# 07_LMS7002M_Power.net
KiCad netlist of a schematic drawn in Altium Designer
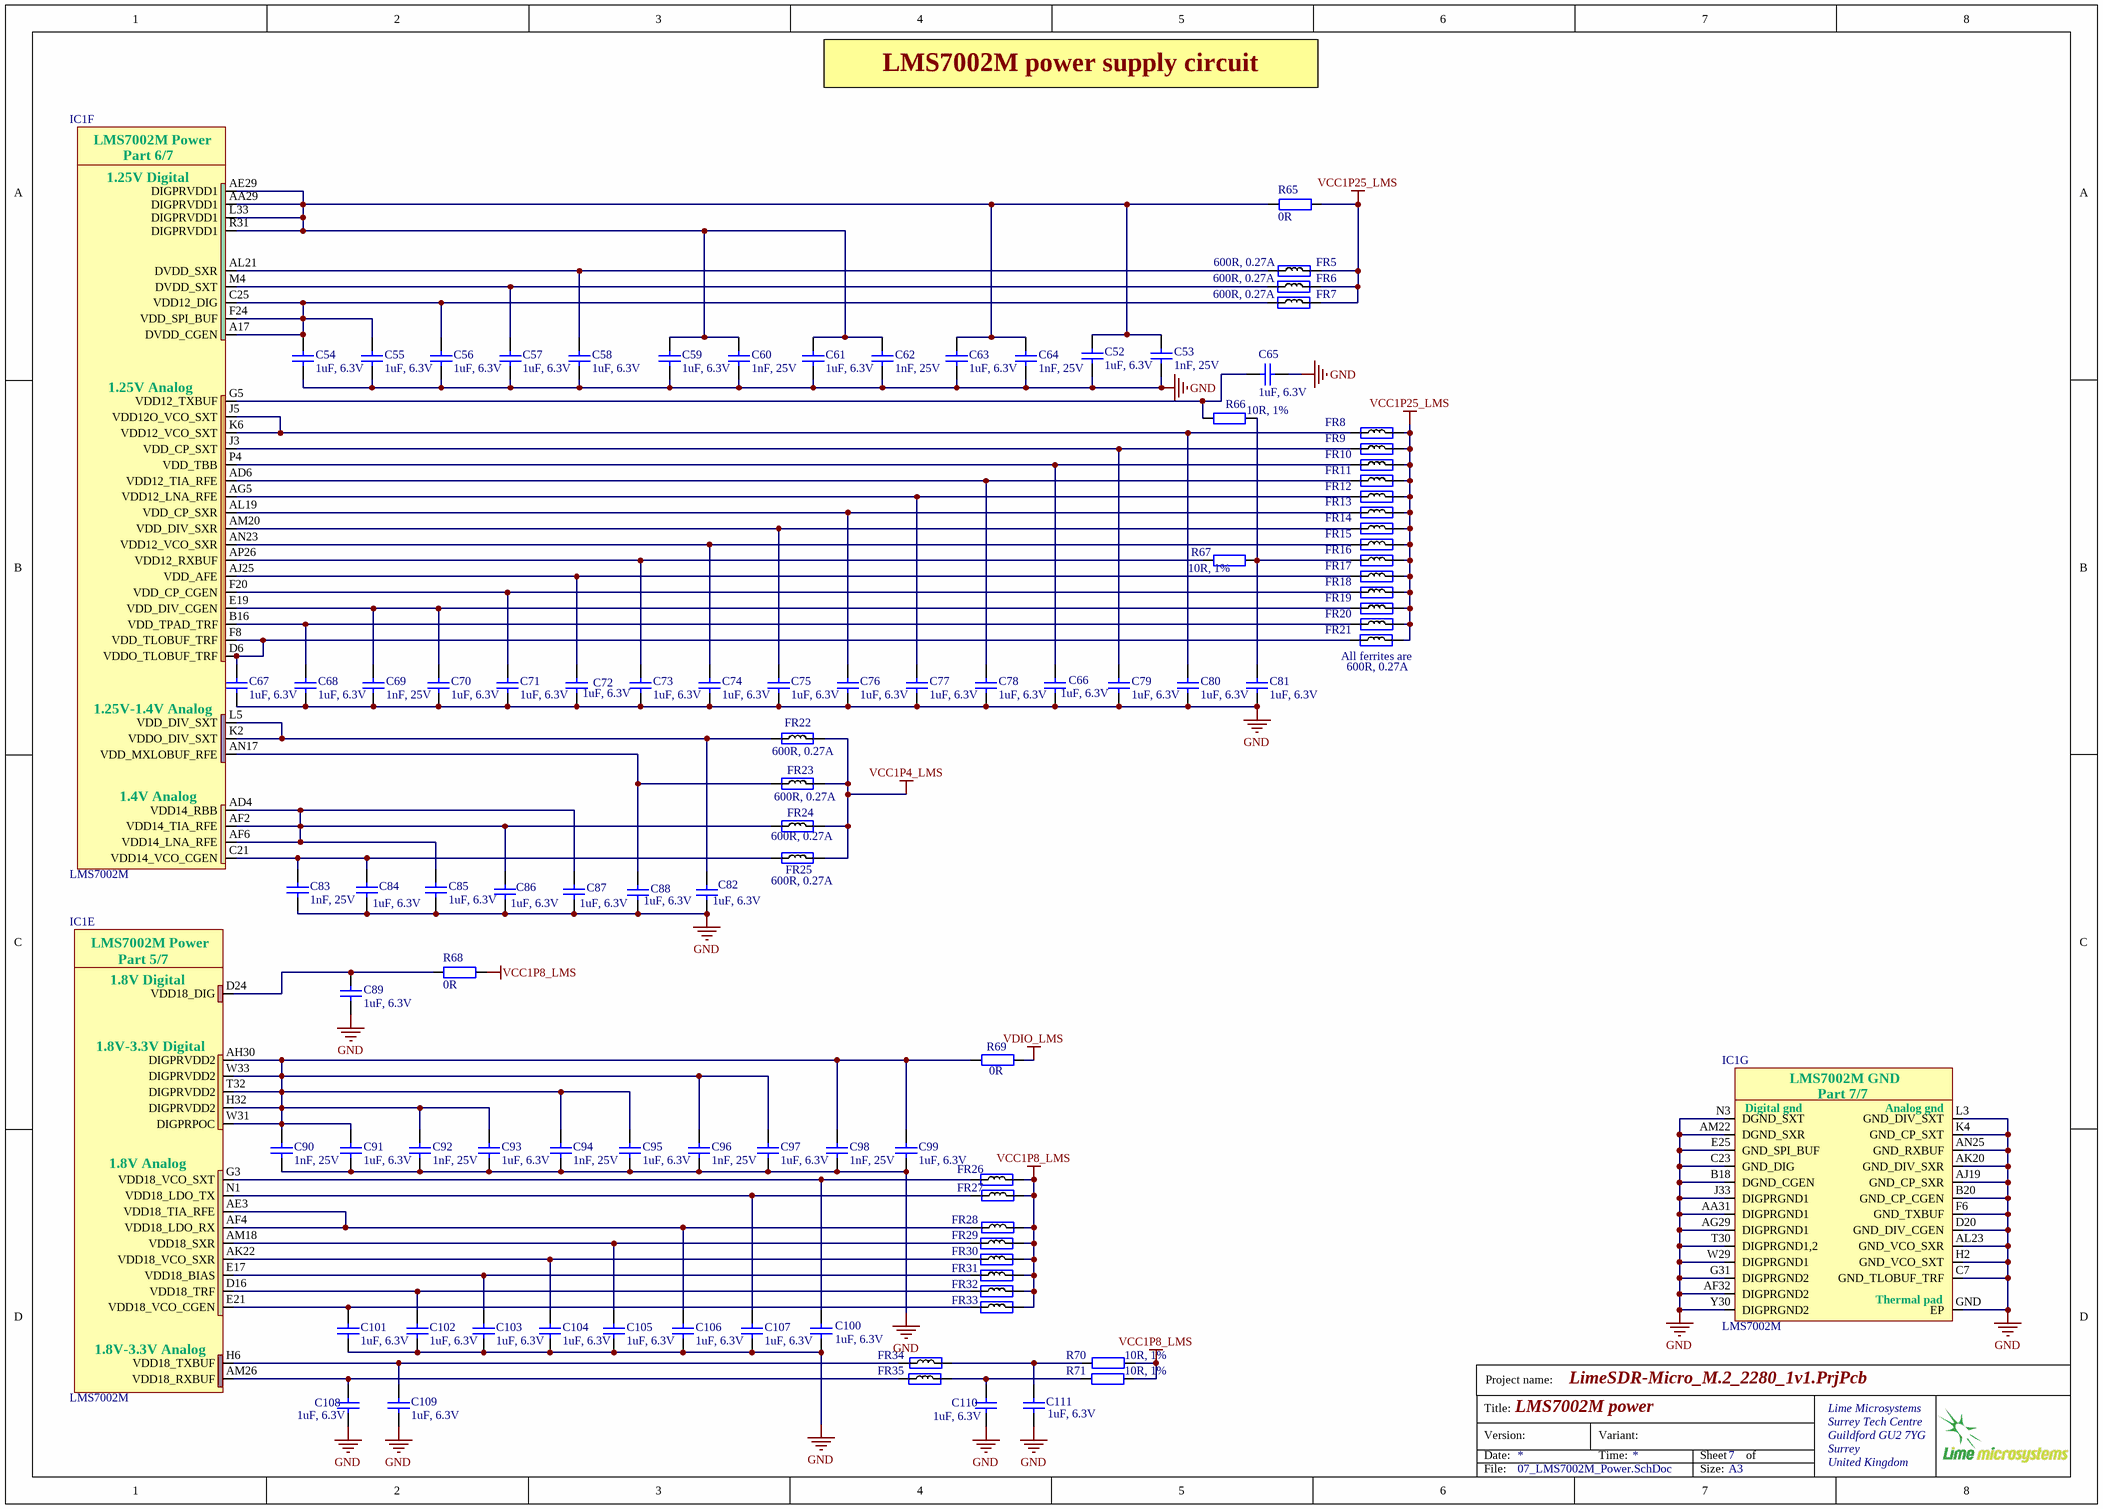
[diagram p0: 07_LMS7002M_Power.SchDoc]

(export (version "E")
  (design (tool "Eeschema 10.0.6"))
  (components
    (comp (ref "C52")
      (value "1uF, 6.3V")
      (footprint "CAP0201")
      (fields (field (name "TOLERANCE") "±20%") (field (name "MANUFACTURER") "TDK Corporation"))
      (libsource (lib "LimeMicroAltiumLib_schLib") (part "Cap_0402"))
    )
    (comp (ref "C53")
      (value "1nF, 25V")
      (footprint "CAP0201")
      (fields (field (name "TOLERANCE") "±10%") (field (name "MANUFACTURER") "TDK Corporation"))
      (libsource (lib "LimeMicroAltiumLib_schLib") (part "Cap_0402"))
    )
    (comp (ref "C54")
      (value "1uF, 6.3V")
      (footprint "CAP0201")
      (fields (field (name "TOLERANCE") "±20%") (field (name "MANUFACTURER") "TDK Corporation"))
      (libsource (lib "LimeMicroAltiumLib_schLib") (part "Cap_0402"))
    )
    (comp (ref "C55")
      (value "1uF, 6.3V")
      (footprint "CAP0201")
      (fields (field (name "TOLERANCE") "±20%") (field (name "MANUFACTURER") "TDK Corporation"))
      (libsource (lib "LimeMicroAltiumLib_schLib") (part "Cap_0402"))
    )
    (comp (ref "C56")
      (value "1uF, 6.3V")
      (footprint "CAP0201")
      (fields (field (name "TOLERANCE") "±20%") (field (name "MANUFACTURER") "TDK Corporation"))
      (libsource (lib "LimeMicroAltiumLib_schLib") (part "Cap_0402"))
    )
    (comp (ref "C57")
      (value "1uF, 6.3V")
      (footprint "CAP0201")
      (fields (field (name "TOLERANCE") "±20%") (field (name "MANUFACTURER") "TDK Corporation"))
      (libsource (lib "LimeMicroAltiumLib_schLib") (part "Cap_0402"))
    )
    (comp (ref "C58")
      (value "1uF, 6.3V")
      (footprint "CAP0201")
      (fields (field (name "TOLERANCE") "±20%") (field (name "MANUFACTURER") "TDK Corporation"))
      (libsource (lib "LimeMicroAltiumLib_schLib") (part "Cap_0402"))
    )
    (comp (ref "C59")
      (value "1uF, 6.3V")
      (footprint "CAP0201")
      (fields (field (name "TOLERANCE") "±20%") (field (name "MANUFACTURER") "TDK Corporation"))
      (libsource (lib "LimeMicroAltiumLib_schLib") (part "Cap_0402"))
    )
    (comp (ref "C60")
      (value "1nF, 25V")
      (footprint "CAP0201")
      (fields (field (name "TOLERANCE") "±10%") (field (name "MANUFACTURER") "TDK Corporation"))
      (libsource (lib "LimeMicroAltiumLib_schLib") (part "Cap_0402"))
    )
    (comp (ref "C61")
      (value "1uF, 6.3V")
      (footprint "CAP0201")
      (fields (field (name "TOLERANCE") "±20%") (field (name "MANUFACTURER") "TDK Corporation"))
      (libsource (lib "LimeMicroAltiumLib_schLib") (part "Cap_0402"))
    )
    (comp (ref "C62")
      (value "1nF, 25V")
      (footprint "CAP0201")
      (fields (field (name "TOLERANCE") "±10%") (field (name "MANUFACTURER") "TDK Corporation"))
      (libsource (lib "LimeMicroAltiumLib_schLib") (part "Cap_0402"))
    )
    (comp (ref "C63")
      (value "1uF, 6.3V")
      (footprint "CAP0201")
      (fields (field (name "TOLERANCE") "±20%") (field (name "MANUFACTURER") "TDK Corporation"))
      (libsource (lib "LimeMicroAltiumLib_schLib") (part "Cap_0402"))
    )
    (comp (ref "C64")
      (value "1nF, 25V")
      (footprint "CAP0201")
      (fields (field (name "TOLERANCE") "±10%") (field (name "MANUFACTURER") "TDK Corporation"))
      (libsource (lib "LimeMicroAltiumLib_schLib") (part "Cap_0402"))
    )
    (comp (ref "C65")
      (value "1uF, 6.3V")
      (footprint "CAP0201")
      (fields (field (name "TOLERANCE") "±20%") (field (name "MANUFACTURER") "TDK Corporation"))
      (libsource (lib "LimeMicroAltiumLib_schLib") (part "Cap_0402"))
    )
    (comp (ref "C66")
      (value "1uF, 6.3V")
      (footprint "CAP0201")
      (fields (field (name "TOLERANCE") "±20%") (field (name "MANUFACTURER") "TDK Corporation"))
      (libsource (lib "LimeMicroAltiumLib_schLib") (part "Cap_0402"))
    )
    (comp (ref "C67")
      (value "1uF, 6.3V")
      (footprint "CAP0201")
      (fields (field (name "TOLERANCE") "±20%") (field (name "MANUFACTURER") "TDK Corporation"))
      (libsource (lib "LimeMicroAltiumLib_schLib") (part "Cap_0402"))
    )
    (comp (ref "C68")
      (value "1uF, 6.3V")
      (footprint "CAP0201")
      (fields (field (name "TOLERANCE") "±20%") (field (name "MANUFACTURER") "TDK Corporation"))
      (libsource (lib "LimeMicroAltiumLib_schLib") (part "Cap_0402"))
    )
    (comp (ref "C69")
      (value "1nF, 25V")
      (footprint "CAP0201")
      (fields (field (name "TOLERANCE") "±10%") (field (name "MANUFACTURER") "TDK Corporation"))
      (libsource (lib "LimeMicroAltiumLib_schLib") (part "Cap_0402"))
    )
    (comp (ref "C70")
      (value "1uF, 6.3V")
      (footprint "CAP0201")
      (fields (field (name "TOLERANCE") "±20%") (field (name "MANUFACTURER") "TDK Corporation"))
      (libsource (lib "LimeMicroAltiumLib_schLib") (part "Cap_0402"))
    )
    (comp (ref "C71")
      (value "1uF, 6.3V")
      (footprint "CAP0201")
      (fields (field (name "TOLERANCE") "±20%") (field (name "MANUFACTURER") "TDK Corporation"))
      (libsource (lib "LimeMicroAltiumLib_schLib") (part "Cap_0402"))
    )
    (comp (ref "C72")
      (value "1uF, 6.3V")
      (footprint "CAP0201")
      (fields (field (name "TOLERANCE") "±20%") (field (name "MANUFACTURER") "TDK Corporation"))
      (libsource (lib "LimeMicroAltiumLib_schLib") (part "Cap_0402"))
    )
    (comp (ref "C73")
      (value "1uF, 6.3V")
      (footprint "CAP0201")
      (fields (field (name "TOLERANCE") "±20%") (field (name "MANUFACTURER") "TDK Corporation"))
      (libsource (lib "LimeMicroAltiumLib_schLib") (part "Cap_0402"))
    )
    (comp (ref "C74")
      (value "1uF, 6.3V")
      (footprint "CAP0201")
      (fields (field (name "TOLERANCE") "±20%") (field (name "MANUFACTURER") "TDK Corporation"))
      (libsource (lib "LimeMicroAltiumLib_schLib") (part "Cap_0402"))
    )
    (comp (ref "C75")
      (value "1uF, 6.3V")
      (footprint "CAP0201")
      (fields (field (name "TOLERANCE") "±20%") (field (name "MANUFACTURER") "TDK Corporation"))
      (libsource (lib "LimeMicroAltiumLib_schLib") (part "Cap_0402"))
    )
    (comp (ref "C76")
      (value "1uF, 6.3V")
      (footprint "CAP0201")
      (fields (field (name "TOLERANCE") "±20%") (field (name "MANUFACTURER") "TDK Corporation"))
      (libsource (lib "LimeMicroAltiumLib_schLib") (part "Cap_0402"))
    )
    (comp (ref "C77")
      (value "1uF, 6.3V")
      (footprint "CAP0201")
      (fields (field (name "TOLERANCE") "±20%") (field (name "MANUFACTURER") "TDK Corporation"))
      (libsource (lib "LimeMicroAltiumLib_schLib") (part "Cap_0402"))
    )
    (comp (ref "C78")
      (value "1uF, 6.3V")
      (footprint "CAP0201")
      (fields (field (name "TOLERANCE") "±20%") (field (name "MANUFACTURER") "TDK Corporation"))
      (libsource (lib "LimeMicroAltiumLib_schLib") (part "Cap_0402"))
    )
    (comp (ref "C79")
      (value "1uF, 6.3V")
      (footprint "CAP0201")
      (fields (field (name "TOLERANCE") "±20%") (field (name "MANUFACTURER") "TDK Corporation"))
      (libsource (lib "LimeMicroAltiumLib_schLib") (part "Cap_0402"))
    )
    (comp (ref "C80")
      (value "1uF, 6.3V")
      (footprint "CAP0201")
      (fields (field (name "TOLERANCE") "±20%") (field (name "MANUFACTURER") "TDK Corporation"))
      (libsource (lib "LimeMicroAltiumLib_schLib") (part "Cap_0402"))
    )
    (comp (ref "C81")
      (value "1uF, 6.3V")
      (footprint "CAP0201")
      (fields (field (name "TOLERANCE") "±20%") (field (name "MANUFACTURER") "TDK Corporation"))
      (libsource (lib "LimeMicroAltiumLib_schLib") (part "Cap_0402"))
    )
    (comp (ref "C82")
      (value "1uF, 6.3V")
      (footprint "CAP0201")
      (fields (field (name "TOLERANCE") "±20%") (field (name "MANUFACTURER") "TDK Corporation"))
      (libsource (lib "LimeMicroAltiumLib_schLib") (part "Cap_0402"))
    )
    (comp (ref "C83")
      (value "1nF, 25V")
      (footprint "CAP0201")
      (fields (field (name "TOLERANCE") "±10%") (field (name "MANUFACTURER") "TDK Corporation"))
      (libsource (lib "LimeMicroAltiumLib_schLib") (part "Cap_0402"))
    )
    (comp (ref "C84")
      (value "1uF, 6.3V")
      (footprint "CAP0201")
      (fields (field (name "TOLERANCE") "±20%") (field (name "MANUFACTURER") "TDK Corporation"))
      (libsource (lib "LimeMicroAltiumLib_schLib") (part "Cap_0402"))
    )
    (comp (ref "C85")
      (value "1uF, 6.3V")
      (footprint "CAP0201")
      (fields (field (name "TOLERANCE") "±20%") (field (name "MANUFACTURER") "TDK Corporation"))
      (libsource (lib "LimeMicroAltiumLib_schLib") (part "Cap_0402"))
    )
    (comp (ref "C86")
      (value "1uF, 6.3V")
      (footprint "CAP0201")
      (fields (field (name "TOLERANCE") "±20%") (field (name "MANUFACTURER") "TDK Corporation"))
      (libsource (lib "LimeMicroAltiumLib_schLib") (part "Cap_0402"))
    )
    (comp (ref "C87")
      (value "1uF, 6.3V")
      (footprint "CAP0201")
      (fields (field (name "TOLERANCE") "±20%") (field (name "MANUFACTURER") "TDK Corporation"))
      (libsource (lib "LimeMicroAltiumLib_schLib") (part "Cap_0402"))
    )
    (comp (ref "C88")
      (value "1uF, 6.3V")
      (footprint "CAP0201")
      (fields (field (name "TOLERANCE") "±20%") (field (name "MANUFACTURER") "TDK Corporation"))
      (libsource (lib "LimeMicroAltiumLib_schLib") (part "Cap_0402"))
    )
    (comp (ref "C89")
      (value "1uF, 6.3V")
      (footprint "CAP0201")
      (fields (field (name "TOLERANCE") "±20%") (field (name "MANUFACTURER") "TDK Corporation"))
      (libsource (lib "LimeMicroAltiumLib_schLib") (part "Cap_0402"))
    )
    (comp (ref "C90")
      (value "1nF, 25V")
      (footprint "CAP0201")
      (fields (field (name "TOLERANCE") "±10%") (field (name "MANUFACTURER") "TDK Corporation"))
      (libsource (lib "LimeMicroAltiumLib_schLib") (part "Cap_0402"))
    )
    (comp (ref "C91")
      (value "1uF, 6.3V")
      (footprint "CAP0201")
      (fields (field (name "TOLERANCE") "±20%") (field (name "MANUFACTURER") "TDK Corporation"))
      (libsource (lib "LimeMicroAltiumLib_schLib") (part "Cap_0402"))
    )
    (comp (ref "C92")
      (value "1nF, 25V")
      (footprint "CAP0201")
      (fields (field (name "TOLERANCE") "±10%") (field (name "MANUFACTURER") "TDK Corporation"))
      (libsource (lib "LimeMicroAltiumLib_schLib") (part "Cap_0402"))
    )
    (comp (ref "C93")
      (value "1uF, 6.3V")
      (footprint "CAP0201")
      (fields (field (name "TOLERANCE") "±20%") (field (name "MANUFACTURER") "TDK Corporation"))
      (libsource (lib "LimeMicroAltiumLib_schLib") (part "Cap_0402"))
    )
    (comp (ref "C94")
      (value "1nF, 25V")
      (footprint "CAP0201")
      (fields (field (name "TOLERANCE") "±10%") (field (name "MANUFACTURER") "TDK Corporation"))
      (libsource (lib "LimeMicroAltiumLib_schLib") (part "Cap_0402"))
    )
    (comp (ref "C95")
      (value "1uF, 6.3V")
      (footprint "CAP0201")
      (fields (field (name "TOLERANCE") "±20%") (field (name "MANUFACTURER") "TDK Corporation"))
      (libsource (lib "LimeMicroAltiumLib_schLib") (part "Cap_0402"))
    )
    (comp (ref "C96")
      (value "1nF, 25V")
      (footprint "CAP0201")
      (fields (field (name "TOLERANCE") "±10%") (field (name "MANUFACTURER") "TDK Corporation"))
      (libsource (lib "LimeMicroAltiumLib_schLib") (part "Cap_0402"))
    )
    (comp (ref "C97")
      (value "1uF, 6.3V")
      (footprint "CAP0201")
      (fields (field (name "TOLERANCE") "±20%") (field (name "MANUFACTURER") "TDK Corporation"))
      (libsource (lib "LimeMicroAltiumLib_schLib") (part "Cap_0402"))
    )
    (comp (ref "C98")
      (value "1nF, 25V")
      (footprint "CAP0201")
      (fields (field (name "TOLERANCE") "±10%") (field (name "MANUFACTURER") "TDK Corporation"))
      (libsource (lib "LimeMicroAltiumLib_schLib") (part "Cap_0402"))
    )
    (comp (ref "C99")
      (value "1uF, 6.3V")
      (footprint "CAP0201")
      (fields (field (name "TOLERANCE") "±20%") (field (name "MANUFACTURER") "TDK Corporation"))
      (libsource (lib "LimeMicroAltiumLib_schLib") (part "Cap_0402"))
    )
    (comp (ref "C100")
      (value "1uF, 6.3V")
      (footprint "CAP0201")
      (fields (field (name "TOLERANCE") "±20%") (field (name "MANUFACTURER") "TDK Corporation"))
      (libsource (lib "LimeMicroAltiumLib_schLib") (part "Cap_0402"))
    )
    (comp (ref "C101")
      (value "1uF, 6.3V")
      (footprint "CAP0201")
      (fields (field (name "TOLERANCE") "±20%") (field (name "MANUFACTURER") "TDK Corporation"))
      (libsource (lib "LimeMicroAltiumLib_schLib") (part "Cap_0402"))
    )
    (comp (ref "C102")
      (value "1uF, 6.3V")
      (footprint "CAP0201")
      (fields (field (name "TOLERANCE") "±20%") (field (name "MANUFACTURER") "TDK Corporation"))
      (libsource (lib "LimeMicroAltiumLib_schLib") (part "Cap_0402"))
    )
    (comp (ref "C103")
      (value "1uF, 6.3V")
      (footprint "CAP0201")
      (fields (field (name "TOLERANCE") "±20%") (field (name "MANUFACTURER") "TDK Corporation"))
      (libsource (lib "LimeMicroAltiumLib_schLib") (part "Cap_0402"))
    )
    (comp (ref "C104")
      (value "1uF, 6.3V")
      (footprint "CAP0201")
      (fields (field (name "TOLERANCE") "±20%") (field (name "MANUFACTURER") "TDK Corporation"))
      (libsource (lib "LimeMicroAltiumLib_schLib") (part "Cap_0402"))
    )
    (comp (ref "C105")
      (value "1uF, 6.3V")
      (footprint "CAP0201")
      (fields (field (name "TOLERANCE") "±20%") (field (name "MANUFACTURER") "TDK Corporation"))
      (libsource (lib "LimeMicroAltiumLib_schLib") (part "Cap_0402"))
    )
    (comp (ref "C106")
      (value "1uF, 6.3V")
      (footprint "CAP0201")
      (fields (field (name "TOLERANCE") "±20%") (field (name "MANUFACTURER") "TDK Corporation"))
      (libsource (lib "LimeMicroAltiumLib_schLib") (part "Cap_0402"))
    )
    (comp (ref "C107")
      (value "1uF, 6.3V")
      (footprint "CAP0201")
      (fields (field (name "TOLERANCE") "±20%") (field (name "MANUFACTURER") "TDK Corporation"))
      (libsource (lib "LimeMicroAltiumLib_schLib") (part "Cap_0402"))
    )
    (comp (ref "C108")
      (value "1uF, 6.3V")
      (footprint "CAP0201")
      (fields (field (name "TOLERANCE") "±20%") (field (name "MANUFACTURER") "TDK Corporation"))
      (libsource (lib "LimeMicroAltiumLib_schLib") (part "Cap_0402"))
    )
    (comp (ref "C109")
      (value "1uF, 6.3V")
      (footprint "CAP0201")
      (fields (field (name "TOLERANCE") "±20%") (field (name "MANUFACTURER") "TDK Corporation"))
      (libsource (lib "LimeMicroAltiumLib_schLib") (part "Cap_0402"))
    )
    (comp (ref "C110")
      (value "1uF, 6.3V")
      (footprint "CAP0201")
      (fields (field (name "TOLERANCE") "±20%") (field (name "MANUFACTURER") "TDK Corporation"))
      (libsource (lib "LimeMicroAltiumLib_schLib") (part "Cap_0402"))
    )
    (comp (ref "C111")
      (value "1uF, 6.3V")
      (footprint "CAP0201")
      (fields (field (name "TOLERANCE") "±20%") (field (name "MANUFACTURER") "TDK Corporation"))
      (libsource (lib "LimeMicroAltiumLib_schLib") (part "Cap_0402"))
    )
    (comp (ref "FR5")
      (value "600R, 0.27A")
      (footprint "RES0201")
      (fields (field (name "MANUFACTURER") "Taiyo Yuden"))
      (libsource (lib "") (part "Ferrite_1"))
    )
    (comp (ref "FR6")
      (value "600R, 0.27A")
      (footprint "RES0201")
      (fields (field (name "MANUFACTURER") "Taiyo Yuden"))
      (libsource (lib "") (part "Ferrite_1"))
    )
    (comp (ref "FR7")
      (value "600R, 0.27A")
      (footprint "RES0201")
      (fields (field (name "MANUFACTURER") "Taiyo Yuden"))
      (libsource (lib "") (part "Ferrite_1"))
    )
    (comp (ref "FR8")
      (value "600R, 0.27A")
      (footprint "RES0201")
      (fields (field (name "MANUFACTURER") "Taiyo Yuden"))
      (libsource (lib "") (part "Ferrite_1"))
    )
    (comp (ref "FR9")
      (value "600R, 0.27A")
      (footprint "RES0201")
      (fields (field (name "MANUFACTURER") "Taiyo Yuden"))
      (libsource (lib "") (part "Ferrite_1"))
    )
    (comp (ref "FR10")
      (value "600R, 0.27A")
      (footprint "RES0201")
      (fields (field (name "MANUFACTURER") "Taiyo Yuden"))
      (libsource (lib "") (part "Ferrite_1"))
    )
    (comp (ref "FR11")
      (value "600R, 0.27A")
      (footprint "RES0201")
      (fields (field (name "MANUFACTURER") "Taiyo Yuden"))
      (libsource (lib "") (part "Ferrite_1"))
    )
    (comp (ref "FR12")
      (value "600R, 0.27A")
      (footprint "RES0201")
      (fields (field (name "MANUFACTURER") "Taiyo Yuden"))
      (libsource (lib "") (part "Ferrite_1"))
    )
    (comp (ref "FR13")
      (value "600R, 0.27A")
      (footprint "RES0201")
      (fields (field (name "MANUFACTURER") "Taiyo Yuden"))
      (libsource (lib "") (part "Ferrite_1"))
    )
    (comp (ref "FR14")
      (value "600R, 0.27A")
      (footprint "RES0201")
      (fields (field (name "MANUFACTURER") "Taiyo Yuden"))
      (libsource (lib "") (part "Ferrite_1"))
    )
    (comp (ref "FR15")
      (value "600R, 0.27A")
      (footprint "RES0201")
      (fields (field (name "MANUFACTURER") "Taiyo Yuden"))
      (libsource (lib "") (part "Ferrite_1"))
    )
    (comp (ref "FR16")
      (value "600R, 0.27A")
      (footprint "RES0201")
      (fields (field (name "MANUFACTURER") "Taiyo Yuden"))
      (libsource (lib "") (part "Ferrite_1"))
    )
    (comp (ref "FR17")
      (value "600R, 0.27A")
      (footprint "RES0201")
      (fields (field (name "MANUFACTURER") "Taiyo Yuden"))
      (libsource (lib "") (part "Ferrite_1"))
    )
    (comp (ref "FR18")
      (value "600R, 0.27A")
      (footprint "RES0201")
      (fields (field (name "MANUFACTURER") "Taiyo Yuden"))
      (libsource (lib "") (part "Ferrite_1"))
    )
    (comp (ref "FR19")
      (value "600R, 0.27A")
      (footprint "RES0201")
      (fields (field (name "MANUFACTURER") "Taiyo Yuden"))
      (libsource (lib "") (part "Ferrite_1"))
    )
    (comp (ref "FR20")
      (value "600R, 0.27A")
      (footprint "RES0201")
      (fields (field (name "MANUFACTURER") "Taiyo Yuden"))
      (libsource (lib "") (part "Ferrite_1"))
    )
    (comp (ref "FR21")
      (value "600R, 0.27A")
      (footprint "RES0201")
      (fields (field (name "MANUFACTURER") "Taiyo Yuden"))
      (libsource (lib "") (part "Ferrite_1"))
    )
    (comp (ref "FR22")
      (value "600R, 0.27A")
      (footprint "RES0201")
      (fields (field (name "MANUFACTURER") "Taiyo Yuden"))
      (libsource (lib "") (part "Ferrite_1"))
    )
    (comp (ref "FR23")
      (value "600R, 0.27A")
      (footprint "RES0201")
      (fields (field (name "MANUFACTURER") "Taiyo Yuden"))
      (libsource (lib "") (part "Ferrite_1"))
    )
    (comp (ref "FR24")
      (value "600R, 0.27A")
      (footprint "RES0201")
      (fields (field (name "MANUFACTURER") "Taiyo Yuden"))
      (libsource (lib "") (part "Ferrite_1"))
    )
    (comp (ref "FR25")
      (value "600R, 0.27A")
      (footprint "RES0201")
      (fields (field (name "MANUFACTURER") "Taiyo Yuden"))
      (libsource (lib "") (part "Ferrite_1"))
    )
    (comp (ref "FR26")
      (value "600R, 0.27A")
      (footprint "RES0201")
      (fields (field (name "MANUFACTURER") "Taiyo Yuden"))
      (libsource (lib "") (part "Ferrite_1"))
    )
    (comp (ref "FR27")
      (value "600R, 0.27A")
      (footprint "RES0201")
      (fields (field (name "MANUFACTURER") "Taiyo Yuden"))
      (libsource (lib "LimeMicroAltiumLib_schLib") (part "Ferrite"))
    )
    (comp (ref "FR28")
      (value "600R, 0.27A")
      (footprint "RES0201")
      (fields (field (name "MANUFACTURER") "Taiyo Yuden"))
      (libsource (lib "LimeMicroAltiumLib_schLib") (part "Ferrite"))
    )
    (comp (ref "FR29")
      (value "600R, 0.27A")
      (footprint "RES0201")
      (fields (field (name "MANUFACTURER") "Taiyo Yuden"))
      (libsource (lib "") (part "Ferrite_1"))
    )
    (comp (ref "FR30")
      (value "600R, 0.27A")
      (footprint "RES0201")
      (fields (field (name "MANUFACTURER") "Taiyo Yuden"))
      (libsource (lib "") (part "Ferrite_1"))
    )
    (comp (ref "FR31")
      (value "600R, 0.27A")
      (footprint "RES0201")
      (fields (field (name "MANUFACTURER") "Taiyo Yuden"))
      (libsource (lib "") (part "Ferrite_1"))
    )
    (comp (ref "FR32")
      (value "600R, 0.27A")
      (footprint "RES0201")
      (fields (field (name "MANUFACTURER") "Taiyo Yuden"))
      (libsource (lib "") (part "Ferrite_1"))
    )
    (comp (ref "FR33")
      (value "600R, 0.27A")
      (footprint "RES0201")
      (fields (field (name "MANUFACTURER") "Taiyo Yuden"))
      (libsource (lib "") (part "Ferrite_1"))
    )
    (comp (ref "FR34")
      (value "600R, 0.27A")
      (footprint "RES0201")
      (fields (field (name "MANUFACTURER") "Taiyo Yuden"))
      (libsource (lib "LimeMicroAltiumLib_schLib") (part "Ferrite"))
    )
    (comp (ref "FR35")
      (value "600R, 0.27A")
      (footprint "RES0201")
      (fields (field (name "MANUFACTURER") "Taiyo Yuden"))
      (libsource (lib "") (part "Ferrite_1"))
    )
    (comp (ref "IC1")
      (value "LMS7002M")
      (footprint "LMS7002M_v5_LESS_SILK")
      (description "Schematic symbol revision 4. Default footprint - 0.31mm pad")
      (fields (field (name "MANUFACTURER") "Lime Microsystems"))
      (libsource (lib "LimeMicroAltiumLib_schLib_r04") (part "LMS7002Mr4"))
    )
    (comp (ref "R65")
      (value "0R")
      (footprint "RES0402")
      (fields (field (name "MANUFACTURER") "Yageo") (field (name "TOLERANCE") "Jumper"))
      (libsource (lib "LimeMicroAltiumLib_schLib") (part "Res_0402"))
    )
    (comp (ref "R66")
      (value "10R, 1%")
      (footprint "RES0201")
      (fields
        (field (name "MANUFACTURER") "Panasonic Electronic Components")
        (field (name "TOLERANCE") "±1%")
      )
      (libsource (lib "LimeMicroAltiumLib_schLib") (part "Res_0402"))
    )
    (comp (ref "R67")
      (value "10R, 1%")
      (footprint "RES0201")
      (fields
        (field (name "MANUFACTURER") "Panasonic Electronic Components")
        (field (name "TOLERANCE") "±1%")
      )
      (libsource (lib "LimeMicroAltiumLib_schLib") (part "Res_0402"))
    )
    (comp (ref "R68")
      (value "0R")
      (footprint "RES0201")
      (fields (field (name "MANUFACTURER") "Yageo") (field (name "TOLERANCE") "5%"))
      (libsource (lib "LimeMicroAltiumLib_schLib") (part "Res_0402"))
    )
    (comp (ref "R69")
      (value "0R")
      (footprint "RES0402")
      (fields (field (name "MANUFACTURER") "Yageo") (field (name "TOLERANCE") "Jumper"))
      (libsource (lib "LimeMicroAltiumLib_schLib") (part "Res_0402"))
    )
    (comp (ref "R70")
      (value "10R, 1%")
      (footprint "RES0201")
      (fields
        (field (name "MANUFACTURER") "Panasonic Electronic Components")
        (field (name "TOLERANCE") "±1%")
      )
      (libsource (lib "LimeMicroAltiumLib_schLib") (part "Res_0402"))
    )
    (comp (ref "R71")
      (value "10R, 1%")
      (footprint "RES0201")
      (fields
        (field (name "MANUFACTURER") "Panasonic Electronic Components")
        (field (name "TOLERANCE") "±1%")
      )
      (libsource (lib "LimeMicroAltiumLib_schLib") (part "Res_0402"))
    )
  )
  (nets
    (net (code "1") (name "GND") (class "Default")
      (node (ref "C100") (pin "2") (pinfunction "2_2") (pintype "passive"))
      (node (ref "C101") (pin "2") (pinfunction "2_2") (pintype "passive"))
      (node (ref "C102") (pin "2") (pinfunction "2_2") (pintype "passive"))
      (node (ref "C103") (pin "2") (pinfunction "2_2") (pintype "passive"))
      (node (ref "C104") (pin "2") (pinfunction "2_2") (pintype "passive"))
      (node (ref "C105") (pin "2") (pinfunction "2_2") (pintype "passive"))
      (node (ref "C106") (pin "2") (pinfunction "2_2") (pintype "passive"))
      (node (ref "C107") (pin "2") (pinfunction "2_2") (pintype "passive"))
      (node (ref "C108") (pin "2") (pinfunction "2_2") (pintype "passive"))
      (node (ref "C109") (pin "2") (pinfunction "2_2") (pintype "passive"))
      (node (ref "C110") (pin "2") (pinfunction "2_2") (pintype "passive"))
      (node (ref "C111") (pin "2") (pinfunction "2_2") (pintype "passive"))
      (node (ref "C52") (pin "2") (pinfunction "2_2") (pintype "passive"))
      (node (ref "C53") (pin "2") (pinfunction "2_2") (pintype "passive"))
      (node (ref "C54") (pin "2") (pinfunction "2_2") (pintype "passive"))
      (node (ref "C55") (pin "2") (pinfunction "2_2") (pintype "passive"))
      (node (ref "C56") (pin "2") (pinfunction "2_2") (pintype "passive"))
      (node (ref "C57") (pin "1") (pinfunction "1_1") (pintype "passive"))
      (node (ref "C58") (pin "2") (pinfunction "2_2") (pintype "passive"))
      (node (ref "C59") (pin "2") (pinfunction "2_2") (pintype "passive"))
      (node (ref "C60") (pin "2") (pinfunction "2_2") (pintype "passive"))
      (node (ref "C61") (pin "2") (pinfunction "2_2") (pintype "passive"))
      (node (ref "C62") (pin "2") (pinfunction "2_2") (pintype "passive"))
      (node (ref "C63") (pin "2") (pinfunction "2_2") (pintype "passive"))
      (node (ref "C64") (pin "2") (pinfunction "2_2") (pintype "passive"))
      (node (ref "C65") (pin "2") (pinfunction "2_2") (pintype "passive"))
      (node (ref "C66") (pin "2") (pinfunction "2_2") (pintype "passive"))
      (node (ref "C67") (pin "2") (pinfunction "2_2") (pintype "passive"))
      (node (ref "C68") (pin "2") (pinfunction "2_2") (pintype "passive"))
      (node (ref "C69") (pin "2") (pinfunction "2_2") (pintype "passive"))
      (node (ref "C70") (pin "2") (pinfunction "2_2") (pintype "passive"))
      (node (ref "C71") (pin "1") (pinfunction "1_1") (pintype "passive"))
      (node (ref "C72") (pin "2") (pinfunction "2_2") (pintype "passive"))
      (node (ref "C73") (pin "2") (pinfunction "2_2") (pintype "passive"))
      (node (ref "C74") (pin "2") (pinfunction "2_2") (pintype "passive"))
      (node (ref "C75") (pin "2") (pinfunction "2_2") (pintype "passive"))
      (node (ref "C76") (pin "2") (pinfunction "2_2") (pintype "passive"))
      (node (ref "C77") (pin "2") (pinfunction "2_2") (pintype "passive"))
      (node (ref "C78") (pin "1") (pinfunction "1_1") (pintype "passive"))
      (node (ref "C79") (pin "2") (pinfunction "2_2") (pintype "passive"))
      (node (ref "C80") (pin "1") (pinfunction "1_1") (pintype "passive"))
      (node (ref "C81") (pin "1") (pinfunction "1_1") (pintype "passive"))
      (node (ref "C82") (pin "2") (pinfunction "2_2") (pintype "passive"))
      (node (ref "C83") (pin "2") (pinfunction "2_2") (pintype "passive"))
      (node (ref "C84") (pin "2") (pinfunction "2_2") (pintype "passive"))
      (node (ref "C85") (pin "2") (pinfunction "2_2") (pintype "passive"))
      (node (ref "C86") (pin "2") (pinfunction "2_2") (pintype "passive"))
      (node (ref "C87") (pin "2") (pinfunction "2_2") (pintype "passive"))
      (node (ref "C88") (pin "2") (pinfunction "2_2") (pintype "passive"))
      (node (ref "C89") (pin "2") (pinfunction "2_2") (pintype "passive"))
      (node (ref "C90") (pin "2") (pinfunction "2_2") (pintype "passive"))
      (node (ref "C91") (pin "2") (pinfunction "2_2") (pintype "passive"))
      (node (ref "C92") (pin "2") (pinfunction "2_2") (pintype "passive"))
      (node (ref "C93") (pin "2") (pinfunction "2_2") (pintype "passive"))
      (node (ref "C94") (pin "2") (pinfunction "2_2") (pintype "passive"))
      (node (ref "C95") (pin "2") (pinfunction "2_2") (pintype "passive"))
      (node (ref "C96") (pin "2") (pinfunction "2_2") (pintype "passive"))
      (node (ref "C97") (pin "2") (pinfunction "2_2") (pintype "passive"))
      (node (ref "C98") (pin "2") (pinfunction "2_2") (pintype "passive"))
      (node (ref "C99") (pin "2") (pinfunction "2_2") (pintype "passive"))
      (node (ref "IC1") (pin "AA31") (pinfunction "DIGPRGND1_AA31") (pintype "passive"))
      (node (ref "IC1") (pin "AF32") (pinfunction "DIGPRGND2_AF32") (pintype "passive"))
      (node (ref "IC1") (pin "AG29") (pinfunction "DIGPRGND1_AG29") (pintype "passive"))
      (node (ref "IC1") (pin "AJ19") (pinfunction "GND_CP_SXR_AJ19") (pintype "passive"))
      (node (ref "IC1") (pin "AK20") (pinfunction "GND_DIV_SXR_AK20") (pintype "passive"))
      (node (ref "IC1") (pin "AL23") (pinfunction "GND_VCO_SXR_AL23") (pintype "passive"))
      (node (ref "IC1") (pin "AM22") (pinfunction "DGND_SXR_AM22") (pintype "passive"))
      (node (ref "IC1") (pin "AN25") (pinfunction "GND_RXBUF_AN25") (pintype "passive"))
      (node (ref "IC1") (pin "B18") (pinfunction "DGND_CGEN_B18") (pintype "passive"))
      (node (ref "IC1") (pin "B20") (pinfunction "GND_CP_CGEN_B20") (pintype "passive"))
      (node (ref "IC1") (pin "C23") (pinfunction "GND_DIG_C23") (pintype "passive"))
      (node (ref "IC1") (pin "C7") (pinfunction "GND_TLOBUF_TRF_C7") (pintype "passive"))
      (node (ref "IC1") (pin "D20") (pinfunction "GND_DIV_CGEN_D20") (pintype "passive"))
      (node (ref "IC1") (pin "E25") (pinfunction "GND_SPI_BUF_E25") (pintype "passive"))
      (node (ref "IC1") (pin "F6") (pinfunction "GND_TXBUF_F6") (pintype "passive"))
      (node (ref "IC1") (pin "G31") (pinfunction "DIGPRGND2_G31") (pintype "passive"))
      (node (ref "IC1") (pin "GND") (pinfunction "EP_GND") (pintype "passive"))
      (node (ref "IC1") (pin "H2") (pinfunction "GND_VCO_SXT_H2") (pintype "passive"))
      (node (ref "IC1") (pin "J33") (pinfunction "DIGPRGND1_J33") (pintype "passive"))
      (node (ref "IC1") (pin "K4") (pinfunction "GND_CP_SXT_K4") (pintype "passive"))
      (node (ref "IC1") (pin "L3") (pinfunction "GND_DIV_SXT_L3") (pintype "passive"))
      (node (ref "IC1") (pin "N3") (pinfunction "DGND_SXT_N3") (pintype "passive"))
      (node (ref "IC1") (pin "T30") (pinfunction "DIGPRGND1,2_T30") (pintype "passive"))
      (node (ref "IC1") (pin "W29") (pinfunction "DIGPRGND1_W29") (pintype "passive"))
      (node (ref "IC1") (pin "Y30") (pinfunction "DIGPRGND2_Y30") (pintype "passive"))
    )
    (net (code "2") (name "Net-(C52-Pad1)") (class "Default")
      (node (ref "C52") (pin "1") (pinfunction "1_1") (pintype "passive"))
      (node (ref "C53") (pin "1") (pinfunction "1_1") (pintype "passive"))
      (node (ref "C59") (pin "1") (pinfunction "1_1") (pintype "passive"))
      (node (ref "C60") (pin "1") (pinfunction "1_1") (pintype "passive"))
      (node (ref "C61") (pin "1") (pinfunction "1_1") (pintype "passive"))
      (node (ref "C62") (pin "1") (pinfunction "1_1") (pintype "passive"))
      (node (ref "C63") (pin "1") (pinfunction "1_1") (pintype "passive"))
      (node (ref "C64") (pin "1") (pinfunction "1_1") (pintype "passive"))
      (node (ref "IC1") (pin "AA29") (pinfunction "DIGPRVDD1_AA29") (pintype "power_in"))
      (node (ref "IC1") (pin "AE29") (pinfunction "DIGPRVDD1_AE29") (pintype "power_in"))
      (node (ref "IC1") (pin "L33") (pinfunction "DIGPRVDD1_L33") (pintype "power_in"))
      (node (ref "IC1") (pin "R31") (pinfunction "DIGPRVDD1_R31") (pintype "power_in"))
      (node (ref "R65") (pin "2") (pinfunction "2_2") (pintype "passive"))
    )
    (net (code "3") (name "Net-(C81-Pad2)") (class "Default")
      (node (ref "C81") (pin "2") (pinfunction "2_2") (pintype "passive"))
      (node (ref "FR16") (pin "1") (pinfunction "1_1") (pintype "passive"))
      (node (ref "R66") (pin "2") (pinfunction "2_2") (pintype "passive"))
      (node (ref "R67") (pin "2") (pinfunction "2_2") (pintype "passive"))
    )
    (net (code "4") (name "Net-(C110-Pad1)") (class "Default")
      (node (ref "C110") (pin "1") (pinfunction "1_1") (pintype "passive"))
      (node (ref "FR35") (pin "2") (pinfunction "2_2") (pintype "passive"))
      (node (ref "R71") (pin "2") (pinfunction "2_2") (pintype "passive"))
    )
    (net (code "5") (name "Net-(C111-Pad1)") (class "Default")
      (node (ref "C111") (pin "1") (pinfunction "1_1") (pintype "passive"))
      (node (ref "FR34") (pin "1") (pinfunction "1_1") (pintype "passive"))
      (node (ref "R70") (pin "1") (pinfunction "1_1") (pintype "passive"))
    )
    (net (code "6") (name "Net-(IC1E-DIGPRPOC)") (class "Default")
      (node (ref "C90") (pin "1") (pinfunction "1_1") (pintype "passive"))
      (node (ref "C91") (pin "1") (pinfunction "1_1") (pintype "passive"))
      (node (ref "C92") (pin "1") (pinfunction "1_1") (pintype "passive"))
      (node (ref "C93") (pin "1") (pinfunction "1_1") (pintype "passive"))
      (node (ref "C94") (pin "1") (pinfunction "1_1") (pintype "passive"))
      (node (ref "C95") (pin "1") (pinfunction "1_1") (pintype "passive"))
      (node (ref "C96") (pin "1") (pinfunction "1_1") (pintype "passive"))
      (node (ref "C97") (pin "1") (pinfunction "1_1") (pintype "passive"))
      (node (ref "C98") (pin "1") (pinfunction "1_1") (pintype "passive"))
      (node (ref "C99") (pin "1") (pinfunction "1_1") (pintype "passive"))
      (node (ref "IC1") (pin "AH30") (pinfunction "DIGPRVDD2_AH30") (pintype "power_in"))
      (node (ref "IC1") (pin "H32") (pinfunction "DIGPRVDD2_H32") (pintype "power_in"))
      (node (ref "IC1") (pin "T32") (pinfunction "DIGPRVDD2_T32") (pintype "power_in"))
      (node (ref "IC1") (pin "W31") (pinfunction "DIGPRPOC_W31") (pintype "power_in"))
      (node (ref "IC1") (pin "W33") (pinfunction "DIGPRVDD2_W33") (pintype "power_in"))
      (node (ref "R69") (pin "2") (pinfunction "2_2") (pintype "passive"))
    )
    (net (code "7") (name "Net-(IC1E-VDD18_BIAS)") (class "Default")
      (node (ref "C103") (pin "1") (pinfunction "1_1") (pintype "passive"))
      (node (ref "FR31") (pin "1") (pinfunction "1_1") (pintype "passive"))
      (node (ref "IC1") (pin "E17") (pinfunction "VDD18_BIAS_E17") (pintype "power_in"))
    )
    (net (code "8") (name "Net-(IC1E-VDD18_DIG)") (class "Default")
      (node (ref "C89") (pin "1") (pinfunction "1_1") (pintype "passive"))
      (node (ref "IC1") (pin "D24") (pinfunction "VDD18_DIG_D24") (pintype "power_in"))
      (node (ref "R68") (pin "1") (pinfunction "1_1") (pintype "passive"))
    )
    (net (code "9") (name "Net-(IC1E-VDD18_LDO_RX)") (class "Default")
      (node (ref "C106") (pin "1") (pinfunction "1_1") (pintype "passive"))
      (node (ref "FR28") (pin "2") (pinfunction "2_2") (pintype "passive"))
      (node (ref "IC1") (pin "AE3") (pinfunction "VDD18_TIA_RFE_AE3") (pintype "power_in"))
      (node (ref "IC1") (pin "AF4") (pinfunction "VDD18_LDO_RX_AF4") (pintype "power_in"))
    )
    (net (code "10") (name "Net-(IC1E-VDD18_LDO_TX)") (class "Default")
      (node (ref "C107") (pin "1") (pinfunction "1_1") (pintype "passive"))
      (node (ref "FR27") (pin "2") (pinfunction "2_2") (pintype "passive"))
      (node (ref "IC1") (pin "N1") (pinfunction "VDD18_LDO_TX_N1") (pintype "power_in"))
    )
    (net (code "11") (name "Net-(IC1E-VDD18_RXBUF)") (class "Default")
      (node (ref "C108") (pin "1") (pinfunction "1_1") (pintype "passive"))
      (node (ref "FR35") (pin "1") (pinfunction "1_1") (pintype "passive"))
      (node (ref "IC1") (pin "AM26") (pinfunction "VDD18_RXBUF_AM26") (pintype "power_in"))
    )
    (net (code "12") (name "Net-(IC1E-VDD18_SXR)") (class "Default")
      (node (ref "C105") (pin "1") (pinfunction "1_1") (pintype "passive"))
      (node (ref "FR29") (pin "1") (pinfunction "1_1") (pintype "passive"))
      (node (ref "IC1") (pin "AM18") (pinfunction "VDD18_SXR_AM18") (pintype "power_in"))
    )
    (net (code "13") (name "Net-(IC1E-VDD18_TRF)") (class "Default")
      (node (ref "C102") (pin "1") (pinfunction "1_1") (pintype "passive"))
      (node (ref "FR32") (pin "1") (pinfunction "1_1") (pintype "passive"))
      (node (ref "IC1") (pin "D16") (pinfunction "VDD18_TRF_D16") (pintype "power_in"))
    )
    (net (code "14") (name "Net-(IC1E-VDD18_TXBUF)") (class "Default")
      (node (ref "C109") (pin "1") (pinfunction "1_1") (pintype "passive"))
      (node (ref "FR34") (pin "2") (pinfunction "2_2") (pintype "passive"))
      (node (ref "IC1") (pin "H6") (pinfunction "VDD18_TXBUF_H6") (pintype "power_in"))
    )
    (net (code "15") (name "Net-(IC1E-VDD18_VCO_CGEN)") (class "Default")
      (node (ref "C101") (pin "1") (pinfunction "1_1") (pintype "passive"))
      (node (ref "FR33") (pin "1") (pinfunction "1_1") (pintype "passive"))
      (node (ref "IC1") (pin "E21") (pinfunction "VDD18_VCO_CGEN_E21") (pintype "power_in"))
    )
    (net (code "16") (name "Net-(IC1E-VDD18_VCO_SXR)") (class "Default")
      (node (ref "C104") (pin "1") (pinfunction "1_1") (pintype "passive"))
      (node (ref "FR30") (pin "1") (pinfunction "1_1") (pintype "passive"))
      (node (ref "IC1") (pin "AK22") (pinfunction "VDD18_VCO_SXR_AK22") (pintype "power_in"))
    )
    (net (code "17") (name "Net-(IC1E-VDD18_VCO_SXT)") (class "Default")
      (node (ref "C100") (pin "1") (pinfunction "1_1") (pintype "passive"))
      (node (ref "FR26") (pin "1") (pinfunction "1_1") (pintype "passive"))
      (node (ref "IC1") (pin "G3") (pinfunction "VDD18_VCO_SXT_G3") (pintype "power_in"))
    )
    (net (code "18") (name "Net-(IC1F-DVDD_CGEN)") (class "Default")
      (node (ref "C54") (pin "1") (pinfunction "1_1") (pintype "passive"))
      (node (ref "C55") (pin "1") (pinfunction "1_1") (pintype "passive"))
      (node (ref "C56") (pin "1") (pinfunction "1_1") (pintype "passive"))
      (node (ref "FR7") (pin "1") (pinfunction "1_1") (pintype "passive"))
      (node (ref "IC1") (pin "A17") (pinfunction "DVDD_CGEN_A17") (pintype "power_in"))
      (node (ref "IC1") (pin "C25") (pinfunction "VDD12_DIG_C25") (pintype "power_in"))
      (node (ref "IC1") (pin "F24") (pinfunction "VDD_SPI_BUF_F24") (pintype "power_in"))
    )
    (net (code "19") (name "Net-(IC1F-DVDD_SXR)") (class "Default")
      (node (ref "C58") (pin "1") (pinfunction "1_1") (pintype "passive"))
      (node (ref "FR5") (pin "1") (pinfunction "1_1") (pintype "passive"))
      (node (ref "IC1") (pin "AL21") (pinfunction "DVDD_SXR_AL21") (pintype "power_in"))
    )
    (net (code "20") (name "Net-(IC1F-DVDD_SXT)") (class "Default")
      (node (ref "C57") (pin "2") (pinfunction "2_2") (pintype "passive"))
      (node (ref "FR6") (pin "1") (pinfunction "1_1") (pintype "passive"))
      (node (ref "IC1") (pin "M4") (pinfunction "DVDD_SXT_M4") (pintype "power_in"))
    )
    (net (code "21") (name "Net-(IC1F-VDD12O_VCO_SXT)") (class "Default")
      (node (ref "C80") (pin "2") (pinfunction "2_2") (pintype "passive"))
      (node (ref "FR8") (pin "1") (pinfunction "1_1") (pintype "passive"))
      (node (ref "IC1") (pin "J5") (pinfunction "VDD12O_VCO_SXT_J5") (pintype "power_in"))
      (node (ref "IC1") (pin "K6") (pinfunction "VDD12_VCO_SXT_K6") (pintype "power_in"))
    )
    (net (code "22") (name "Net-(IC1F-VDD12_LNA_RFE)") (class "Default")
      (node (ref "C77") (pin "1") (pinfunction "1_1") (pintype "passive"))
      (node (ref "FR12") (pin "1") (pinfunction "1_1") (pintype "passive"))
      (node (ref "IC1") (pin "AG5") (pinfunction "VDD12_LNA_RFE_AG5") (pintype "power_in"))
    )
    (net (code "23") (name "Net-(IC1F-VDD12_RXBUF)") (class "Default")
      (node (ref "C73") (pin "1") (pinfunction "1_1") (pintype "passive"))
      (node (ref "IC1") (pin "AP26") (pinfunction "VDD12_RXBUF_AP26") (pintype "power_in"))
      (node (ref "R67") (pin "1") (pinfunction "1_1") (pintype "passive"))
    )
    (net (code "24") (name "Net-(IC1F-VDD12_TIA_RFE)") (class "Default")
      (node (ref "C78") (pin "2") (pinfunction "2_2") (pintype "passive"))
      (node (ref "FR11") (pin "1") (pinfunction "1_1") (pintype "passive"))
      (node (ref "IC1") (pin "AD6") (pinfunction "VDD12_TIA_RFE_AD6") (pintype "power_in"))
    )
    (net (code "25") (name "Net-(IC1F-VDD12_TXBUF)") (class "Default")
      (node (ref "C65") (pin "1") (pinfunction "1_1") (pintype "passive"))
      (node (ref "IC1") (pin "G5") (pinfunction "VDD12_TXBUF_G5") (pintype "power_in"))
      (node (ref "R66") (pin "1") (pinfunction "1_1") (pintype "passive"))
    )
    (net (code "26") (name "Net-(IC1F-VDD12_VCO_SXR)") (class "Default")
      (node (ref "C74") (pin "1") (pinfunction "1_1") (pintype "passive"))
      (node (ref "FR15") (pin "1") (pinfunction "1_1") (pintype "passive"))
      (node (ref "IC1") (pin "AN23") (pinfunction "VDD12_VCO_SXR_AN23") (pintype "power_in"))
    )
    (net (code "27") (name "Net-(IC1F-VDD14_LNA_RFE)") (class "Default")
      (node (ref "C85") (pin "1") (pinfunction "1_1") (pintype "passive"))
      (node (ref "C86") (pin "1") (pinfunction "1_1") (pintype "passive"))
      (node (ref "C87") (pin "1") (pinfunction "1_1") (pintype "passive"))
      (node (ref "FR24") (pin "1") (pinfunction "1_1") (pintype "passive"))
      (node (ref "IC1") (pin "AD4") (pinfunction "VDD14_RBB_AD4") (pintype "power_in"))
      (node (ref "IC1") (pin "AF2") (pinfunction "VDD14_TIA_RFE_AF2") (pintype "power_in"))
      (node (ref "IC1") (pin "AF6") (pinfunction "VDD14_LNA_RFE_AF6") (pintype "power_in"))
    )
    (net (code "28") (name "Net-(IC1F-VDD14_VCO_CGEN)") (class "Default")
      (node (ref "C83") (pin "1") (pinfunction "1_1") (pintype "passive"))
      (node (ref "C84") (pin "1") (pinfunction "1_1") (pintype "passive"))
      (node (ref "FR25") (pin "1") (pinfunction "1_1") (pintype "passive"))
      (node (ref "IC1") (pin "C21") (pinfunction "VDD14_VCO_CGEN_C21") (pintype "power_in"))
    )
    (net (code "29") (name "Net-(IC1F-VDDO_DIV_SXT)") (class "Default")
      (node (ref "C82") (pin "1") (pinfunction "1_1") (pintype "passive"))
      (node (ref "FR22") (pin "1") (pinfunction "1_1") (pintype "passive"))
      (node (ref "IC1") (pin "K2") (pinfunction "VDDO_DIV_SXT_K2") (pintype "power_in"))
      (node (ref "IC1") (pin "L5") (pinfunction "VDD_DIV_SXT_L5") (pintype "power_in"))
    )
    (net (code "30") (name "Net-(IC1F-VDDO_TLOBUF_TRF)") (class "Default")
      (node (ref "C67") (pin "1") (pinfunction "1_1") (pintype "passive"))
      (node (ref "FR21") (pin "1") (pinfunction "1_1") (pintype "passive"))
      (node (ref "IC1") (pin "D6") (pinfunction "VDDO_TLOBUF_TRF_D6") (pintype "power_in"))
      (node (ref "IC1") (pin "F8") (pinfunction "VDD_TLOBUF_TRF_F8") (pintype "power_in"))
    )
    (net (code "31") (name "Net-(IC1F-VDD_AFE)") (class "Default")
      (node (ref "C72") (pin "1") (pinfunction "1_1") (pintype "passive"))
      (node (ref "FR17") (pin "1") (pinfunction "1_1") (pintype "passive"))
      (node (ref "IC1") (pin "AJ25") (pinfunction "VDD_AFE_AJ25") (pintype "power_in"))
    )
    (net (code "32") (name "Net-(IC1F-VDD_CP_CGEN)") (class "Default")
      (node (ref "C71") (pin "2") (pinfunction "2_2") (pintype "passive"))
      (node (ref "FR18") (pin "1") (pinfunction "1_1") (pintype "passive"))
      (node (ref "IC1") (pin "F20") (pinfunction "VDD_CP_CGEN_F20") (pintype "power_in"))
    )
    (net (code "33") (name "Net-(IC1F-VDD_CP_SXR)") (class "Default")
      (node (ref "C76") (pin "1") (pinfunction "1_1") (pintype "passive"))
      (node (ref "FR13") (pin "1") (pinfunction "1_1") (pintype "passive"))
      (node (ref "IC1") (pin "AL19") (pinfunction "VDD_CP_SXR_AL19") (pintype "power_in"))
    )
    (net (code "34") (name "Net-(IC1F-VDD_CP_SXT)") (class "Default")
      (node (ref "C79") (pin "1") (pinfunction "1_1") (pintype "passive"))
      (node (ref "FR9") (pin "1") (pinfunction "1_1") (pintype "passive"))
      (node (ref "IC1") (pin "J3") (pinfunction "VDD_CP_SXT_J3") (pintype "power_in"))
    )
    (net (code "35") (name "Net-(IC1F-VDD_DIV_CGEN)") (class "Default")
      (node (ref "C69") (pin "1") (pinfunction "1_1") (pintype "passive"))
      (node (ref "C70") (pin "1") (pinfunction "1_1") (pintype "passive"))
      (node (ref "FR19") (pin "1") (pinfunction "1_1") (pintype "passive"))
      (node (ref "IC1") (pin "E19") (pinfunction "VDD_DIV_CGEN_E19") (pintype "power_in"))
    )
    (net (code "36") (name "Net-(IC1F-VDD_DIV_SXR)") (class "Default")
      (node (ref "C75") (pin "1") (pinfunction "1_1") (pintype "passive"))
      (node (ref "FR14") (pin "1") (pinfunction "1_1") (pintype "passive"))
      (node (ref "IC1") (pin "AM20") (pinfunction "VDD_DIV_SXR_AM20") (pintype "power_in"))
    )
    (net (code "37") (name "Net-(IC1F-VDD_MXLOBUF_RFE)") (class "Default")
      (node (ref "C88") (pin "1") (pinfunction "1_1") (pintype "passive"))
      (node (ref "FR23") (pin "1") (pinfunction "1_1") (pintype "passive"))
      (node (ref "IC1") (pin "AN17") (pinfunction "VDD_MXLOBUF_RFE_AN17") (pintype "power_in"))
    )
    (net (code "38") (name "Net-(IC1F-VDD_TBB)") (class "Default")
      (node (ref "C66") (pin "1") (pinfunction "1_1") (pintype "passive"))
      (node (ref "FR10") (pin "1") (pinfunction "1_1") (pintype "passive"))
      (node (ref "IC1") (pin "P4") (pinfunction "VDD_TBB_P4") (pintype "power_in"))
    )
    (net (code "39") (name "Net-(IC1F-VDD_TPAD_TRF)") (class "Default")
      (node (ref "C68") (pin "1") (pinfunction "1_1") (pintype "passive"))
      (node (ref "FR20") (pin "1") (pinfunction "1_1") (pintype "passive"))
      (node (ref "IC1") (pin "B16") (pinfunction "VDD_TPAD_TRF_B16") (pintype "power_in"))
    )
    (net (code "40") (name "VCC1P4_LMS") (class "Default")
      (node (ref "FR22") (pin "2") (pinfunction "2_2") (pintype "passive"))
      (node (ref "FR23") (pin "2") (pinfunction "2_2") (pintype "passive"))
      (node (ref "FR24") (pin "2") (pinfunction "2_2") (pintype "passive"))
      (node (ref "FR25") (pin "2") (pinfunction "2_2") (pintype "passive"))
    )
    (net (code "41") (name "VCC1P8_LMS") (class "Default")
      (node (ref "FR26") (pin "2") (pinfunction "2_2") (pintype "passive"))
      (node (ref "FR27") (pin "1") (pinfunction "1_1") (pintype "passive"))
      (node (ref "FR28") (pin "1") (pinfunction "1_1") (pintype "passive"))
      (node (ref "FR29") (pin "2") (pinfunction "2_2") (pintype "passive"))
      (node (ref "FR30") (pin "2") (pinfunction "2_2") (pintype "passive"))
      (node (ref "FR31") (pin "2") (pinfunction "2_2") (pintype "passive"))
      (node (ref "FR32") (pin "2") (pinfunction "2_2") (pintype "passive"))
      (node (ref "FR33") (pin "2") (pinfunction "2_2") (pintype "passive"))
      (node (ref "R68") (pin "2") (pinfunction "2_2") (pintype "passive"))
      (node (ref "R70") (pin "2") (pinfunction "2_2") (pintype "passive"))
      (node (ref "R71") (pin "1") (pinfunction "1_1") (pintype "passive"))
    )
    (net (code "42") (name "VCC1P25_LMS") (class "Default")
      (node (ref "FR10") (pin "2") (pinfunction "2_2") (pintype "passive"))
      (node (ref "FR11") (pin "2") (pinfunction "2_2") (pintype "passive"))
      (node (ref "FR12") (pin "2") (pinfunction "2_2") (pintype "passive"))
      (node (ref "FR13") (pin "2") (pinfunction "2_2") (pintype "passive"))
      (node (ref "FR14") (pin "2") (pinfunction "2_2") (pintype "passive"))
      (node (ref "FR15") (pin "2") (pinfunction "2_2") (pintype "passive"))
      (node (ref "FR16") (pin "2") (pinfunction "2_2") (pintype "passive"))
      (node (ref "FR17") (pin "2") (pinfunction "2_2") (pintype "passive"))
      (node (ref "FR18") (pin "2") (pinfunction "2_2") (pintype "passive"))
      (node (ref "FR19") (pin "2") (pinfunction "2_2") (pintype "passive"))
      (node (ref "FR20") (pin "2") (pinfunction "2_2") (pintype "passive"))
      (node (ref "FR21") (pin "2") (pinfunction "2_2") (pintype "passive"))
      (node (ref "FR5") (pin "2") (pinfunction "2_2") (pintype "passive"))
      (node (ref "FR6") (pin "2") (pinfunction "2_2") (pintype "passive"))
      (node (ref "FR7") (pin "2") (pinfunction "2_2") (pintype "passive"))
      (node (ref "FR8") (pin "2") (pinfunction "2_2") (pintype "passive"))
      (node (ref "FR9") (pin "2") (pinfunction "2_2") (pintype "passive"))
      (node (ref "R65") (pin "1") (pinfunction "1_1") (pintype "passive"))
    )
    (net (code "43") (name "VDIO_LMS") (class "Default")
      (node (ref "R69") (pin "1") (pinfunction "1_1") (pintype "passive"))
    )
  )
)
